# mcu.net
KiCad netlist of a schematic drawn in Altium Designer
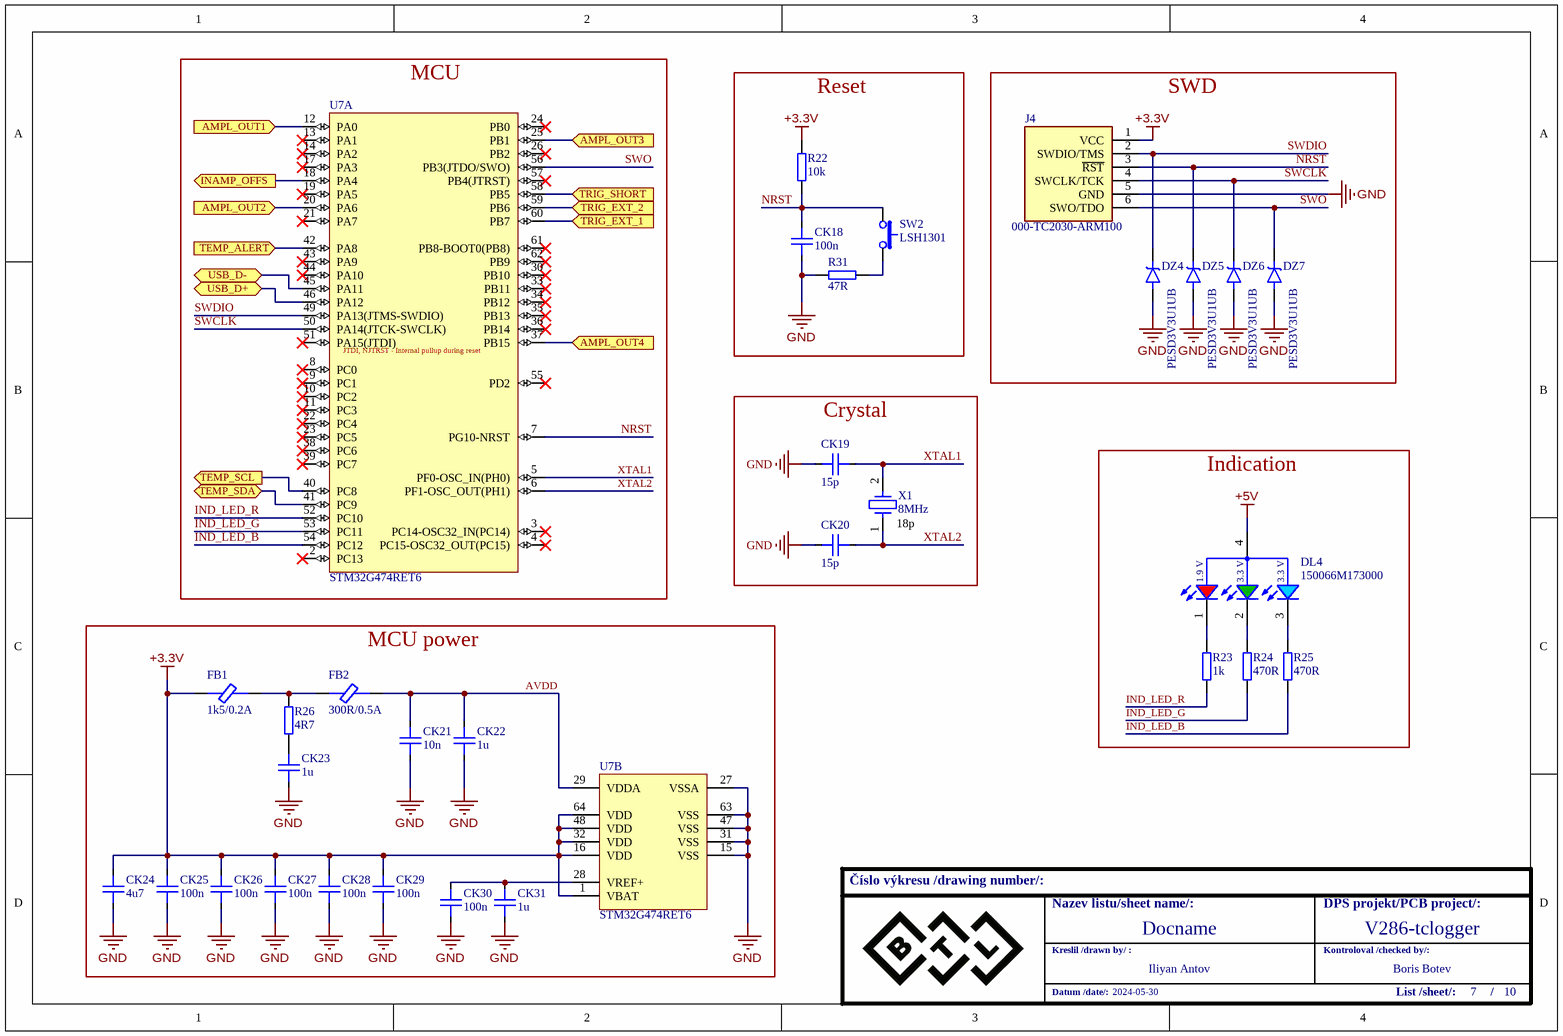
[diagram p0: mcu.SchDoc]

(export (version "E")
  (design (tool "Eeschema 10.0.6"))
  (components
    (comp (ref "CK18")
      (value "100n")
      (footprint "CAPC1608X09N(SMC0603)")
      (description "C; 100n; 100V; 10%; X7R; ??;")
      (fields
        (field (name "MANUFACTURER") "Murata Electronics: GRM188R72A104KA35D;;Yageo: CC0603KRX7R0BB104")
      )
      (libsource (lib "altium_sql") (part "CK"))
    )
    (comp (ref "CK19")
      (value "15p")
      (footprint "CAPC1608X09N(SMC0603)")
      (description "C; 15p; 25V; 5%; NP0/C0G; ??;")
      (fields (field (name "MANUFACTURER") "Samsung: CL10C150JB81PNC"))
      (libsource (lib "altium_sql") (part "CK"))
    )
    (comp (ref "CK20")
      (value "15p")
      (footprint "CAPC1608X09N(SMC0603)")
      (description "C; 15p; 25V; 5%; NP0/C0G; ??;")
      (fields (field (name "MANUFACTURER") "Samsung: CL10C150JB81PNC"))
      (libsource (lib "altium_sql") (part "CK"))
    )
    (comp (ref "CK21")
      (value "10n")
      (footprint "CAPC1608X09N(SMC0603)")
      (description "C; 10n; 50V; 5%; NP0/C0G; ??;")
      (fields (field (name "MANUFACTURER") "TDK: C1608C0G1H103J080AA"))
      (libsource (lib "altium_sql") (part "CK"))
    )
    (comp (ref "CK22")
      (value "1u")
      (footprint "CAPC1608X09N(SMC0603)")
      (description "C; 1u; 50V; 10%; X5R; ??;")
      (libsource (lib "altium_sql") (part "CK"))
    )
    (comp (ref "CK23")
      (value "1u")
      (footprint "CAPC1608X09N(SMC0603)")
      (description "C; 1u; 50V; 10%; X5R; ??;")
      (libsource (lib "altium_sql") (part "CK"))
    )
    (comp (ref "CK24")
      (value "4u7")
      (footprint "CAPC1608X09N(SMC0603)")
      (description "C; 4u7; 25V; 20%; X5R; ??;")
      (fields (field (name "MANUFACTURER") "TDK Corporation: C1608X5R1E475M080AC"))
      (libsource (lib "altium_sql") (part "CK"))
    )
    (comp (ref "CK25")
      (value "100n")
      (footprint "CAPC1608X09N(SMC0603)")
      (description "C; 100n; 100V; 10%; X7R; ??;")
      (fields
        (field (name "MANUFACTURER") "Murata Electronics: GRM188R72A104KA35D;;Yageo: CC0603KRX7R0BB104")
      )
      (libsource (lib "altium_sql") (part "CK"))
    )
    (comp (ref "CK26")
      (value "100n")
      (footprint "CAPC1608X09N(SMC0603)")
      (description "C; 100n; 100V; 10%; X7R; ??;")
      (fields
        (field (name "MANUFACTURER") "Murata Electronics: GRM188R72A104KA35D;;Yageo: CC0603KRX7R0BB104")
      )
      (libsource (lib "altium_sql") (part "CK"))
    )
    (comp (ref "CK27")
      (value "100n")
      (footprint "CAPC1608X09N(SMC0603)")
      (description "C; 100n; 100V; 10%; X7R; ??;")
      (fields
        (field (name "MANUFACTURER") "Murata Electronics: GRM188R72A104KA35D;;Yageo: CC0603KRX7R0BB104")
      )
      (libsource (lib "altium_sql") (part "CK"))
    )
    (comp (ref "CK28")
      (value "100n")
      (footprint "CAPC1608X09N(SMC0603)")
      (description "C; 100n; 100V; 10%; X7R; ??;")
      (fields
        (field (name "MANUFACTURER") "Murata Electronics: GRM188R72A104KA35D;;Yageo: CC0603KRX7R0BB104")
      )
      (libsource (lib "altium_sql") (part "CK"))
    )
    (comp (ref "CK29")
      (value "100n")
      (footprint "CAPC1608X09N(SMC0603)")
      (description "C; 100n; 100V; 10%; X7R; ??;")
      (fields
        (field (name "MANUFACTURER") "Murata Electronics: GRM188R72A104KA35D;;Yageo: CC0603KRX7R0BB104")
      )
      (libsource (lib "altium_sql") (part "CK"))
    )
    (comp (ref "CK30")
      (value "100n")
      (footprint "CAPC1608X09N(SMC0603)")
      (description "C; 100n; 100V; 10%; X7R; ??;")
      (fields
        (field (name "MANUFACTURER") "Murata Electronics: GRM188R72A104KA35D;;Yageo: CC0603KRX7R0BB104")
      )
      (libsource (lib "altium_sql") (part "CK"))
    )
    (comp (ref "CK31")
      (value "1u")
      (footprint "CAPC1608X09N(SMC0603)")
      (description "C; 1u; 50V; 10%; X5R; ??;")
      (libsource (lib "altium_sql") (part "CK"))
    )
    (comp (ref "DL4")
      (value "150066M173000")
      (footprint "WE_150066M173000")
      (description "Ind; Light; Red/Green/Blue;")
      (fields (field (name "MANUFACTURER") "Würth: 150066M173000"))
      (libsource (lib "altium_sql") (part "EDL+150066M173000X00"))
    )
    (comp (ref "DZ4")
      (value "PESD3V3U1UB")
      (footprint "SODFL160X65-2N(SC79)")
      (description "CP; Voltage [V] - Unidirectional; 4.5; R:Yes; 1x;")
      (fields (field (name "MANUFACTURER") "Nexperia: PESD3V3U1UB,115;;NXP: PESD3V3U1UB,115"))
      (libsource (lib "altium_sql") (part "DTU"))
    )
    (comp (ref "DZ5")
      (value "PESD3V3U1UB")
      (footprint "SODFL160X65-2N(SC79)")
      (description "CP; Voltage [V] - Unidirectional; 4.5; R:Yes; 1x;")
      (fields (field (name "MANUFACTURER") "Nexperia: PESD3V3U1UB,115;;NXP: PESD3V3U1UB,115"))
      (libsource (lib "altium_sql") (part "DTU"))
    )
    (comp (ref "DZ6")
      (value "PESD3V3U1UB")
      (footprint "SODFL160X65-2N(SC79)")
      (description "CP; Voltage [V] - Unidirectional; 4.5; R:Yes; 1x;")
      (fields (field (name "MANUFACTURER") "Nexperia: PESD3V3U1UB,115;;NXP: PESD3V3U1UB,115"))
      (libsource (lib "altium_sql") (part "DTU"))
    )
    (comp (ref "DZ7")
      (value "PESD3V3U1UB")
      (footprint "SODFL160X65-2N(SC79)")
      (description "CP; Voltage [V] - Unidirectional; 4.5; R:Yes; 1x;")
      (fields (field (name "MANUFACTURER") "Nexperia: PESD3V3U1UB,115;;NXP: PESD3V3U1UB,115"))
      (libsource (lib "altium_sql") (part "DTU"))
    )
    (comp (ref "FB1")
      (value "1k5/0.2A")
      (footprint "INDC2012X08N(SML0805)")
      (description "Flt; Chip Bead; 0.7Ohm; 0.2A; ??V; 1x;")
      (libsource (lib "altium_sql") (part "L_FB"))
    )
    (comp (ref "FB2")
      (value "300R/0.5A")
      (footprint "MMZ1608")
      (description "Flt; Chip Bead; 0.25Ohm; 0.5A; ??V; 1x;")
      (fields (field (name "MANUFACTURER") "TDK: MMZ1608B301CTAH0;;TDK: MMZ1608B301CT"))
      (libsource (lib "altium_sql") (part "L_FB"))
    )
    (comp (ref "J4")
      (value "000-TC2030-ARM100")
      (footprint "TC2030-MCP-NL")
      (description "De; Programming connector;")
      (libsource (lib "altium_sql") (part "000-TC2030-ARM100"))
    )
    (comp (ref "R22")
      (value "10k")
      (footprint "RESC2012X06N(SMR0805)")
      (description "R; 10k; 0.125W; 1%; 150V; Thick Film; ±100ppm/K; 1x;")
      (libsource (lib "altium_sql") (part "R"))
    )
    (comp (ref "R23")
      (value "1k")
      (footprint "RESC2012X06N(SMR0805)")
      (description "R; 1k; 0.125W; 1%; 150V; Thick Film; ±100ppm/K; 1x;")
      (libsource (lib "altium_sql") (part "R"))
    )
    (comp (ref "R24")
      (value "470R")
      (footprint "RESC1608X06N(SMR0603)")
      (description "R; 470R; 0.1W; 1%; 75V; Thick Film; ±100ppm/K; 1x;")
      (fields (field (name "MANUFACTURER") "Yageo: RC0603FR-07470RL;;Panasonic: ERJ3EKF4700V"))
      (libsource (lib "altium_sql") (part "R"))
    )
    (comp (ref "R25")
      (value "470R")
      (footprint "RESC1608X06N(SMR0603)")
      (description "R; 470R; 0.1W; 1%; 75V; Thick Film; ±100ppm/K; 1x;")
      (fields (field (name "MANUFACTURER") "Yageo: RC0603FR-07470RL;;Panasonic: ERJ3EKF4700V"))
      (libsource (lib "altium_sql") (part "R"))
    )
    (comp (ref "R26")
      (value "4R7")
      (footprint "RESC2012X06N(SMR0805)")
      (description "R; 4R7; 0.125W; 5%; 150V; Thick Film; ±200ppm/K; 1x;")
      (fields (field (name "MANUFACTURER") "YAGEO: RC0805FR-074R7L;;BC Components: MCU0805-50 1% P5 4R7"))
      (libsource (lib "altium_sql") (part "R"))
    )
    (comp (ref "R31")
      (value "47R")
      (footprint "RESC2012X06N(SMR0805)")
      (description "R; 47R; 0.125W; 1%; 150V; Thick Film; ±100ppm/K; 1x;")
      (libsource (lib "altium_sql") (part "R"))
    )
    (comp (ref "SW2")
      (value "LSH1301")
      (footprint "LSH_SWITCH")
      (description "MSw; SPST; PCB; 1x; DC:12V; DC:0.05A; AC:??V; AC:??A; CV:??V; Push-button;")
      (fields (field (name "MANUFACTURER") "DIPTRONICS: DTSM-62N-V-T/R"))
      (libsource (lib "altium_sql") (part "ESW+LSH1301XX0"))
    )
    (comp (ref "U7")
      (value "STM32G474RET6")
      (footprint "TSQFP50P1200X1200X160-64M")
      (libsource (lib "") (part "STM32G474RET6_1"))
    )
    (comp (ref "X1")
      (value "8MHz")
      (footprint "TXC_7A")
      (description "Oth; Crystal;")
      (fields (field (name "MANUFACTURER") "Abracon: ABM3-8.000MHZ-D2Y-T"))
      (libsource (lib "altium_sql") (part "XTAL_2PIN_1"))
    )
  )
  (nets
    (net (code "1") (name "+3.3V") (class "Default")
      (node (ref "CK24") (pin "2") (pinfunction "2_2") (pintype "passive"))
      (node (ref "CK25") (pin "2") (pinfunction "2_2") (pintype "passive"))
      (node (ref "CK26") (pin "2") (pinfunction "2_2") (pintype "passive"))
      (node (ref "CK27") (pin "2") (pinfunction "2_2") (pintype "passive"))
      (node (ref "CK28") (pin "2") (pinfunction "2_2") (pintype "passive"))
      (node (ref "CK29") (pin "2") (pinfunction "2_2") (pintype "passive"))
      (node (ref "FB1") (pin "1") (pinfunction "L1A_1") (pintype "passive"))
      (node (ref "J4") (pin "1") (pinfunction "VCC_1") (pintype "power_in"))
      (node (ref "R22") (pin "2") (pinfunction "2_2") (pintype "passive"))
      (node (ref "U7") (pin "1") (pinfunction "VBAT_1") (pintype "power_in"))
      (node (ref "U7") (pin "16") (pinfunction "VDD_16") (pintype "power_in"))
      (node (ref "U7") (pin "32") (pinfunction "VDD_32") (pintype "power_in"))
      (node (ref "U7") (pin "48") (pinfunction "VDD_48") (pintype "power_in"))
      (node (ref "U7") (pin "64") (pinfunction "VDD_64") (pintype "power_in"))
    )
    (net (code "2") (name "+5V") (class "Default")
      (node (ref "DL4") (pin "4") (pinfunction "A_4") (pintype "passive"))
    )
    (net (code "3") (name "/AMPL_OUT1") (class "Default")
      (node (ref "U7") (pin "12") (pinfunction "PA0_12") (pintype "bidirectional"))
    )
    (net (code "4") (name "/AMPL_OUT2") (class "Default")
      (node (ref "U7") (pin "20") (pinfunction "PA6_20") (pintype "bidirectional"))
    )
    (net (code "5") (name "/AMPL_OUT3") (class "Default")
      (node (ref "U7") (pin "25") (pinfunction "PB1_25") (pintype "bidirectional"))
    )
    (net (code "6") (name "/AMPL_OUT4") (class "Default")
      (node (ref "U7") (pin "37") (pinfunction "PB15_37") (pintype "bidirectional"))
    )
    (net (code "7") (name "/AVDD") (class "Default")
      (node (ref "CK21") (pin "2") (pinfunction "2_2") (pintype "passive"))
      (node (ref "CK22") (pin "1") (pinfunction "1_1") (pintype "passive"))
      (node (ref "FB2") (pin "2") (pinfunction "L1B_2") (pintype "passive"))
      (node (ref "U7") (pin "29") (pinfunction "VDDA_29") (pintype "power_in"))
    )
    (net (code "8") (name "/INAMP_OFFS") (class "Default")
      (node (ref "U7") (pin "18") (pinfunction "PA4_18") (pintype "bidirectional"))
    )
    (net (code "9") (name "/IND_LED_B") (class "Default")
      (node (ref "R25") (pin "1") (pinfunction "1_1") (pintype "passive"))
      (node (ref "U7") (pin "54") (pinfunction "PC12_54") (pintype "bidirectional"))
    )
    (net (code "10") (name "/IND_LED_G") (class "Default")
      (node (ref "R24") (pin "1") (pinfunction "1_1") (pintype "passive"))
      (node (ref "U7") (pin "53") (pinfunction "PC11_53") (pintype "bidirectional"))
    )
    (net (code "11") (name "/IND_LED_R") (class "Default")
      (node (ref "R23") (pin "2") (pinfunction "2_2") (pintype "passive"))
      (node (ref "U7") (pin "52") (pinfunction "PC10_52") (pintype "bidirectional"))
    )
    (net (code "12") (name "/NRST") (class "Default")
      (node (ref "CK18") (pin "2") (pinfunction "2_2") (pintype "passive"))
      (node (ref "DZ5") (pin "1") (pinfunction "C_1") (pintype "passive"))
      (node (ref "J4") (pin "3") (pinfunction "~{RST}_3") (pintype "passive"))
      (node (ref "R22") (pin "1") (pinfunction "1_1") (pintype "passive"))
      (node (ref "SW2") (pin "1") (pintype "passive"))
      (node (ref "U7") (pin "7") (pinfunction "PG10-NRST_7") (pintype "bidirectional"))
    )
    (net (code "13") (name "/SWCLK") (class "Default")
      (node (ref "DZ6") (pin "1") (pinfunction "C_1") (pintype "passive"))
      (node (ref "J4") (pin "4") (pinfunction "SWCLK/TCK_4") (pintype "passive"))
      (node (ref "U7") (pin "50") (pinfunction "PA14(JTCK-SWCLK)_50") (pintype "bidirectional"))
    )
    (net (code "14") (name "/SWDIO") (class "Default")
      (node (ref "DZ4") (pin "1") (pinfunction "C_1") (pintype "passive"))
      (node (ref "J4") (pin "2") (pinfunction "SWDIO/TMS_2") (pintype "passive"))
      (node (ref "U7") (pin "49") (pinfunction "PA13(JTMS-SWDIO)_49") (pintype "bidirectional"))
    )
    (net (code "15") (name "/SWO") (class "Default")
      (node (ref "DZ7") (pin "1") (pinfunction "C_1") (pintype "passive"))
      (node (ref "J4") (pin "6") (pinfunction "SWO/TDO_6") (pintype "passive"))
      (node (ref "U7") (pin "56") (pinfunction "PB3(JTDO/SWO)_56") (pintype "bidirectional"))
    )
    (net (code "16") (name "/TEMP_ALERT") (class "Default")
      (node (ref "U7") (pin "42") (pinfunction "PA8_42") (pintype "bidirectional"))
    )
    (net (code "17") (name "/TEMP_SCL") (class "Default")
      (node (ref "U7") (pin "40") (pinfunction "PC8_40") (pintype "bidirectional"))
    )
    (net (code "18") (name "/TEMP_SDA") (class "Default")
      (node (ref "U7") (pin "41") (pinfunction "PC9_41") (pintype "bidirectional"))
    )
    (net (code "19") (name "/TRIG_EXT_1") (class "Default")
      (node (ref "U7") (pin "60") (pinfunction "PB7_60") (pintype "bidirectional"))
    )
    (net (code "20") (name "/TRIG_EXT_2") (class "Default")
      (node (ref "U7") (pin "59") (pinfunction "PB6_59") (pintype "bidirectional"))
    )
    (net (code "21") (name "/TRIG_SHORT") (class "Default")
      (node (ref "U7") (pin "58") (pinfunction "PB5_58") (pintype "bidirectional"))
    )
    (net (code "22") (name "/USB_D+") (class "Default")
      (node (ref "U7") (pin "46") (pinfunction "PA12_46") (pintype "bidirectional"))
    )
    (net (code "23") (name "/USB_D-") (class "Default")
      (node (ref "U7") (pin "45") (pinfunction "PA11_45") (pintype "bidirectional"))
    )
    (net (code "24") (name "/XTAL1") (class "Default")
      (node (ref "CK19") (pin "1") (pinfunction "1_1") (pintype "passive"))
      (node (ref "U7") (pin "5") (pinfunction "PF0-OSC_IN(PH0)_5") (pintype "bidirectional"))
      (node (ref "X1") (pin "2") (pintype "passive"))
    )
    (net (code "25") (name "/XTAL2") (class "Default")
      (node (ref "CK20") (pin "1") (pinfunction "1_1") (pintype "passive"))
      (node (ref "U7") (pin "6") (pinfunction "PF1-OSC_OUT(PH1)_6") (pintype "bidirectional"))
      (node (ref "X1") (pin "1") (pintype "passive"))
    )
    (net (code "26") (name "GND") (class "Default")
      (node (ref "CK18") (pin "1") (pinfunction "1_1") (pintype "passive"))
      (node (ref "CK19") (pin "2") (pinfunction "2_2") (pintype "passive"))
      (node (ref "CK20") (pin "2") (pinfunction "2_2") (pintype "passive"))
      (node (ref "CK21") (pin "1") (pinfunction "1_1") (pintype "passive"))
      (node (ref "CK22") (pin "2") (pinfunction "2_2") (pintype "passive"))
      (node (ref "CK23") (pin "2") (pinfunction "2_2") (pintype "passive"))
      (node (ref "CK24") (pin "1") (pinfunction "1_1") (pintype "passive"))
      (node (ref "CK25") (pin "1") (pinfunction "1_1") (pintype "passive"))
      (node (ref "CK26") (pin "1") (pinfunction "1_1") (pintype "passive"))
      (node (ref "CK27") (pin "1") (pinfunction "1_1") (pintype "passive"))
      (node (ref "CK28") (pin "1") (pinfunction "1_1") (pintype "passive"))
      (node (ref "CK29") (pin "1") (pinfunction "1_1") (pintype "passive"))
      (node (ref "CK30") (pin "1") (pinfunction "1_1") (pintype "passive"))
      (node (ref "CK31") (pin "2") (pinfunction "2_2") (pintype "passive"))
      (node (ref "DZ4") (pin "2") (pinfunction "A_2") (pintype "passive"))
      (node (ref "DZ5") (pin "2") (pinfunction "A_2") (pintype "passive"))
      (node (ref "DZ6") (pin "2") (pinfunction "A_2") (pintype "passive"))
      (node (ref "DZ7") (pin "2") (pinfunction "A_2") (pintype "passive"))
      (node (ref "J4") (pin "5") (pinfunction "GND_5") (pintype "power_in"))
      (node (ref "R31") (pin "2") (pinfunction "2_2") (pintype "passive"))
      (node (ref "U7") (pin "15") (pinfunction "VSS_15") (pintype "power_in"))
      (node (ref "U7") (pin "27") (pinfunction "VSSA_27") (pintype "power_in"))
      (node (ref "U7") (pin "31") (pinfunction "VSS_31") (pintype "power_in"))
      (node (ref "U7") (pin "47") (pinfunction "VSS_47") (pintype "power_in"))
      (node (ref "U7") (pin "63") (pinfunction "VSS_63") (pintype "power_in"))
    )
    (net (code "27") (name "Net-(CK23-Pad1)") (class "Default")
      (node (ref "CK23") (pin "1") (pinfunction "1_1") (pintype "passive"))
      (node (ref "R26") (pin "1") (pinfunction "1_1") (pintype "passive"))
    )
    (net (code "28") (name "Net-(DL4-K-Pad1)") (class "Default")
      (node (ref "DL4") (pin "1") (pinfunction "K_1") (pintype "passive"))
      (node (ref "R23") (pin "1") (pinfunction "1_1") (pintype "passive"))
    )
    (net (code "29") (name "Net-(DL4-K-Pad2)") (class "Default")
      (node (ref "DL4") (pin "2") (pinfunction "K_2") (pintype "passive"))
      (node (ref "R24") (pin "2") (pinfunction "2_2") (pintype "passive"))
    )
    (net (code "30") (name "Net-(DL4-K-Pad3)") (class "Default")
      (node (ref "DL4") (pin "3") (pinfunction "K_3") (pintype "passive"))
      (node (ref "R25") (pin "2") (pinfunction "2_2") (pintype "passive"))
    )
    (net (code "31") (name "Net-(FB1-L1B)") (class "Default")
      (node (ref "FB1") (pin "2") (pinfunction "L1B_2") (pintype "passive"))
      (node (ref "FB2") (pin "1") (pinfunction "L1A_1") (pintype "passive"))
      (node (ref "R26") (pin "2") (pinfunction "2_2") (pintype "passive"))
    )
    (net (code "32") (name "Net-(R31-Pad1)") (class "Default")
      (node (ref "R31") (pin "1") (pinfunction "1_1") (pintype "passive"))
      (node (ref "SW2") (pin "3") (pintype "passive"))
    )
    (net (code "33") (name "Net-(U7B-VREF+)") (class "Default")
      (node (ref "CK30") (pin "2") (pinfunction "2_2") (pintype "passive"))
      (node (ref "CK31") (pin "1") (pinfunction "1_1") (pintype "passive"))
      (node (ref "U7") (pin "28") (pinfunction "VREF+_28") (pintype "power_in"))
    )
    (net (code "34") (name "unconnected-(U7A-PA1-Pad13)") (class "Default")
      (node (ref "U7") (pin "13") (pinfunction "PA1_13") (pintype "bidirectional+no_connect"))
    )
    (net (code "35") (name "unconnected-(U7A-PA2-Pad14)") (class "Default")
      (node (ref "U7") (pin "14") (pinfunction "PA2_14") (pintype "bidirectional+no_connect"))
    )
    (net (code "36") (name "unconnected-(U7A-PA3-Pad17)") (class "Default")
      (node (ref "U7") (pin "17") (pinfunction "PA3_17") (pintype "bidirectional+no_connect"))
    )
    (net (code "37") (name "unconnected-(U7A-PA5-Pad19)") (class "Default")
      (node (ref "U7") (pin "19") (pinfunction "PA5_19") (pintype "bidirectional+no_connect"))
    )
    (net (code "38") (name "unconnected-(U7A-PA7-Pad21)") (class "Default")
      (node (ref "U7") (pin "21") (pinfunction "PA7_21") (pintype "bidirectional+no_connect"))
    )
    (net (code "39") (name "unconnected-(U7A-PA9-Pad43)") (class "Default")
      (node (ref "U7") (pin "43") (pinfunction "PA9_43") (pintype "bidirectional+no_connect"))
    )
    (net (code "40") (name "unconnected-(U7A-PA10-Pad44)") (class "Default")
      (node (ref "U7") (pin "44") (pinfunction "PA10_44") (pintype "bidirectional+no_connect"))
    )
    (net (code "41") (name "unconnected-(U7A-PA15(JTDI)-Pad51)") (class "Default")
      (node (ref "U7") (pin "51") (pinfunction "PA15(JTDI)_51") (pintype "bidirectional+no_connect"))
    )
    (net (code "42") (name "unconnected-(U7A-PB0-Pad24)") (class "Default")
      (node (ref "U7") (pin "24") (pinfunction "PB0_24") (pintype "bidirectional+no_connect"))
    )
    (net (code "43") (name "unconnected-(U7A-PB2-Pad26)") (class "Default")
      (node (ref "U7") (pin "26") (pinfunction "PB2_26") (pintype "bidirectional+no_connect"))
    )
    (net (code "44") (name "unconnected-(U7A-PB4(JTRST)-Pad57)") (class "Default")
      (node (ref "U7") (pin "57") (pinfunction "PB4(JTRST)_57") (pintype "bidirectional+no_connect"))
    )
    (net (code "45") (name "unconnected-(U7A-PB8-BOOT0(PB8)-Pad61)") (class "Default")
      (node (ref "U7") (pin "61") (pinfunction "PB8-BOOT0(PB8)_61") (pintype "bidirectional+no_connect"))
    )
    (net (code "46") (name "unconnected-(U7A-PB9-Pad62)") (class "Default")
      (node (ref "U7") (pin "62") (pinfunction "PB9_62") (pintype "bidirectional+no_connect"))
    )
    (net (code "47") (name "unconnected-(U7A-PB10-Pad30)") (class "Default")
      (node (ref "U7") (pin "30") (pinfunction "PB10_30") (pintype "bidirectional+no_connect"))
    )
    (net (code "48") (name "unconnected-(U7A-PB11-Pad33)") (class "Default")
      (node (ref "U7") (pin "33") (pinfunction "PB11_33") (pintype "bidirectional+no_connect"))
    )
    (net (code "49") (name "unconnected-(U7A-PB12-Pad34)") (class "Default")
      (node (ref "U7") (pin "34") (pinfunction "PB12_34") (pintype "bidirectional+no_connect"))
    )
    (net (code "50") (name "unconnected-(U7A-PB13-Pad35)") (class "Default")
      (node (ref "U7") (pin "35") (pinfunction "PB13_35") (pintype "bidirectional+no_connect"))
    )
    (net (code "51") (name "unconnected-(U7A-PB14-Pad36)") (class "Default")
      (node (ref "U7") (pin "36") (pinfunction "PB14_36") (pintype "bidirectional+no_connect"))
    )
    (net (code "52") (name "unconnected-(U7A-PC0-Pad8)") (class "Default")
      (node (ref "U7") (pin "8") (pinfunction "PC0_8") (pintype "bidirectional+no_connect"))
    )
    (net (code "53") (name "unconnected-(U7A-PC1-Pad9)") (class "Default")
      (node (ref "U7") (pin "9") (pinfunction "PC1_9") (pintype "bidirectional+no_connect"))
    )
    (net (code "54") (name "unconnected-(U7A-PC2-Pad10)") (class "Default")
      (node (ref "U7") (pin "10") (pinfunction "PC2_10") (pintype "bidirectional+no_connect"))
    )
    (net (code "55") (name "unconnected-(U7A-PC3-Pad11)") (class "Default")
      (node (ref "U7") (pin "11") (pinfunction "PC3_11") (pintype "bidirectional+no_connect"))
    )
    (net (code "56") (name "unconnected-(U7A-PC4-Pad22)") (class "Default")
      (node (ref "U7") (pin "22") (pinfunction "PC4_22") (pintype "bidirectional+no_connect"))
    )
    (net (code "57") (name "unconnected-(U7A-PC5-Pad23)") (class "Default")
      (node (ref "U7") (pin "23") (pinfunction "PC5_23") (pintype "bidirectional+no_connect"))
    )
    (net (code "58") (name "unconnected-(U7A-PC6-Pad38)") (class "Default")
      (node (ref "U7") (pin "38") (pinfunction "PC6_38") (pintype "bidirectional+no_connect"))
    )
    (net (code "59") (name "unconnected-(U7A-PC7-Pad39)") (class "Default")
      (node (ref "U7") (pin "39") (pinfunction "PC7_39") (pintype "bidirectional+no_connect"))
    )
    (net (code "60") (name "unconnected-(U7A-PC13-Pad2)") (class "Default")
      (node (ref "U7") (pin "2") (pinfunction "PC13_2") (pintype "bidirectional+no_connect"))
    )
    (net (code "61") (name "unconnected-(U7A-PC14-OSC32_IN(PC14)-Pad3)") (class "Default")
      (node (ref "U7") (pin "3") (pinfunction "PC14-OSC32_IN(PC14)_3") (pintype "bidirectional+no_connect"))
    )
    (net (code "62") (name "unconnected-(U7A-PC15-OSC32_OUT(PC15)-Pad4)") (class "Default")
      (node (ref "U7") (pin "4") (pinfunction "PC15-OSC32_OUT(PC15)_4") (pintype "bidirectional+no_connect"))
    )
    (net (code "63") (name "unconnected-(U7A-PD2-Pad55)") (class "Default")
      (node (ref "U7") (pin "55") (pinfunction "PD2_55") (pintype "bidirectional+no_connect"))
    )
  )
)
